# PIC32_WIZ810MJ.net
KiCad netlist of a schematic drawn in EAGLE
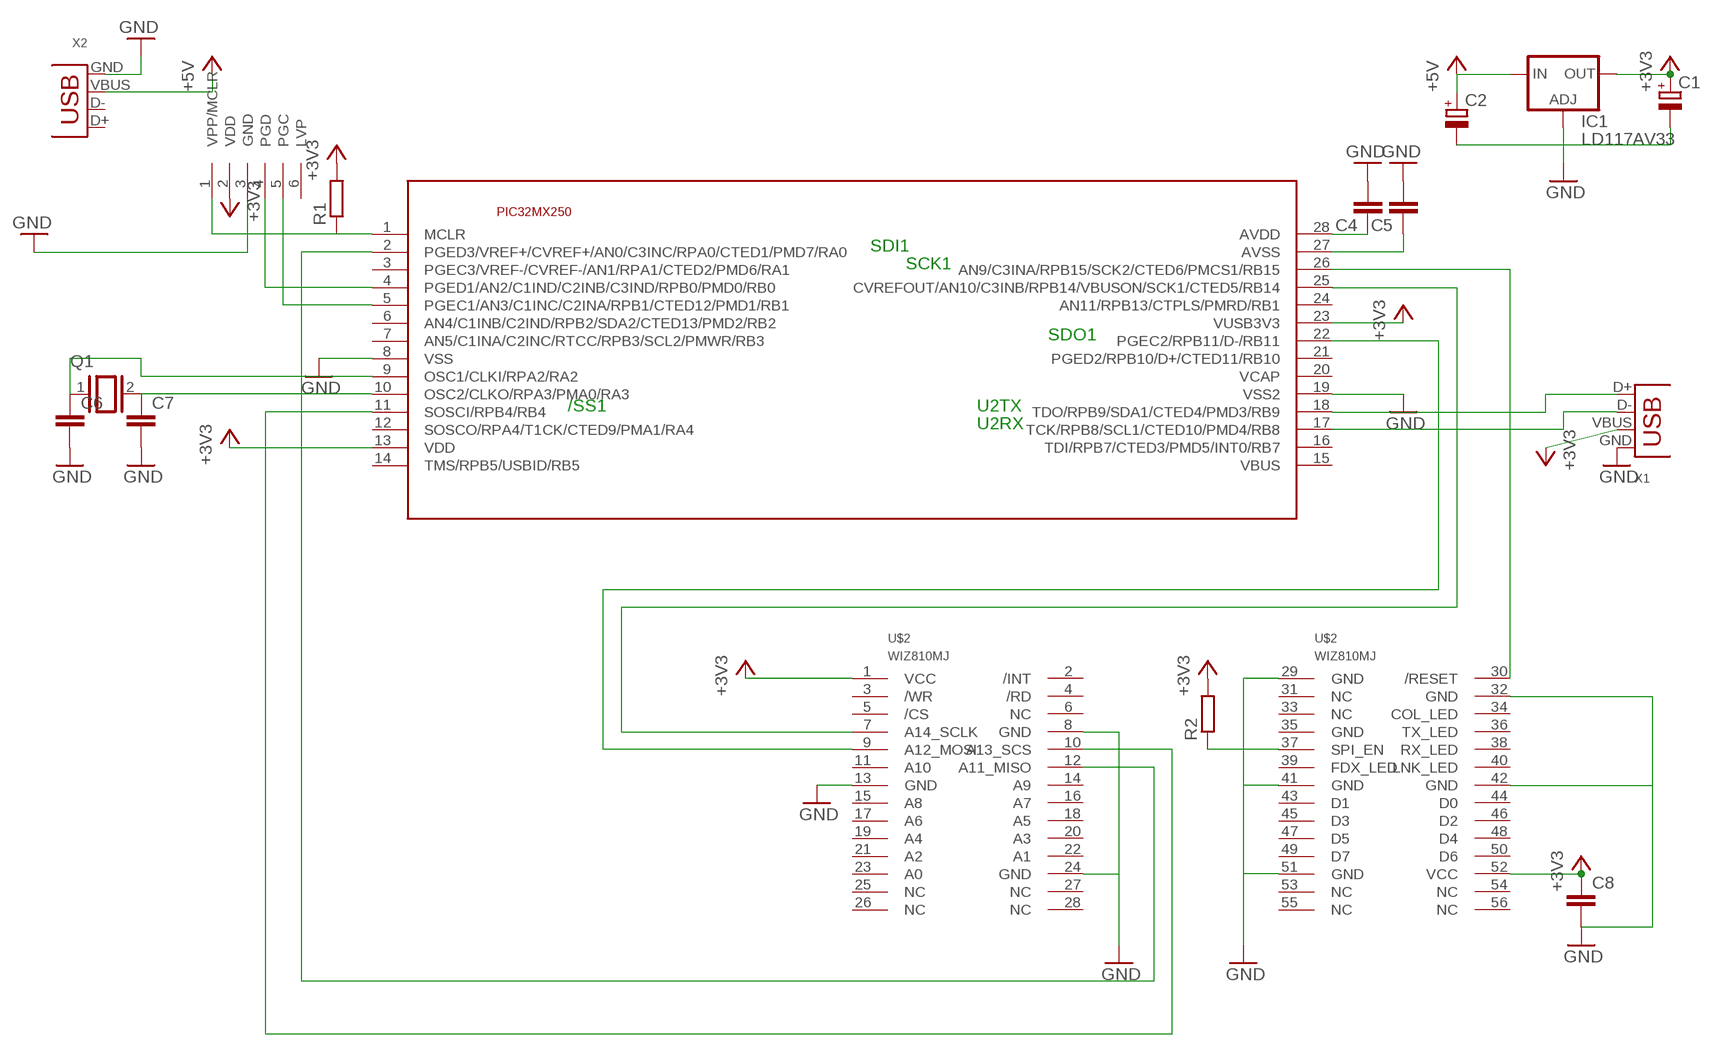
[diagram p0: schematic, sheet 1]

(export (version "E")
  (design (tool "Eeschema 10.0.6"))
  (components
    (comp (ref "C1")
      (value "CPOL-EUE3.5-10")
      (footprint "eagle-import:E3,5-10")
      (libsource (lib "eagle-import") (part "CPOL-EUE3.5-10"))
    )
    (comp (ref "C2")
      (value "CPOL-EUE3.5-10")
      (footprint "eagle-import:E3,5-10")
      (libsource (lib "eagle-import") (part "CPOL-EUE3.5-10"))
    )
    (comp (ref "C4")
      (value "C-EU050-055X075")
      (footprint "eagle-import:C050-055X075")
      (libsource (lib "eagle-import") (part "C-EU050-055X075"))
    )
    (comp (ref "C5")
      (value "C-EU050-055X075")
      (footprint "eagle-import:C050-055X075")
      (libsource (lib "eagle-import") (part "C-EU050-055X075"))
    )
    (comp (ref "C6")
      (value "C-EU025-025X050")
      (footprint "eagle-import:C025-025X050")
      (libsource (lib "eagle-import") (part "C-EU025-025X050"))
    )
    (comp (ref "C7")
      (value "C-EU025-025X050")
      (footprint "eagle-import:C025-025X050")
      (libsource (lib "eagle-import") (part "C-EU025-025X050"))
    )
    (comp (ref "C8")
      (value "C-EU050-055X075")
      (footprint "eagle-import:C050-055X075")
      (libsource (lib "eagle-import") (part "C-EU050-055X075"))
    )
    (comp (ref "IC1")
      (value "LD117AV33")
      (footprint "eagle-import:TO220L1")
      (libsource (lib "eagle-import") (part "LD117A?V33"))
    )
    (comp (ref "Q1")
      (value "XTAL/S")
      (footprint "eagle-import:QS")
      (libsource (lib "eagle-import") (part "XTAL/S"))
    )
    (comp (ref "R1")
      (value "R-EU_0204/5")
      (footprint "eagle-import:0204_5")
      (libsource (lib "eagle-import") (part "R-EU_0204/5"))
    )
    (comp (ref "R2")
      (value "R-EU_0204/5")
      (footprint "eagle-import:0204_5")
      (libsource (lib "eagle-import") (part "R-EU_0204/5"))
    )
    (comp (ref "U$1")
      (value "PIC32MX2XXDIP28_SLIM")
      (footprint "eagle-import:DIP254P762X508-28")
      (libsource (lib "eagle-import") (part "PIC32MX2XXDIP28_SLIM"))
    )
    (comp (ref "U$2")
      (value "WIZ810MJ")
      (footprint "eagle-import:WIZ810MJ")
      (libsource (lib "eagle-import") (part "WIZ810MJ"))
    )
    (comp (ref "U$3")
      (value "ICSP-6_6P")
      (footprint "eagle-import:1X06-CLEANBIG")
      (libsource (lib "eagle-import") (part "ICSP-6_6P"))
    )
    (comp (ref "X1")
      (value "USB-A-H")
      (footprint "eagle-import:USB-A-H")
      (libsource (lib "eagle-import") (part "USB-A-H"))
    )
    (comp (ref "X2")
      (value "USB-B-H")
      (footprint "eagle-import:USB-B-H")
      (libsource (lib "eagle-import") (part "USB-B-H"))
    )
  )
  (nets
    (net (code "1") (name "+3V3") (class "Default")
      (node (ref "C1") (pin "+") (pinfunction "+_+") (pintype "passive"))
      (node (ref "C8") (pin "1") (pinfunction "1_1") (pintype "passive"))
      (node (ref "IC1") (pin "2") (pinfunction "OUT_2") (pintype "passive"))
      (node (ref "R1") (pin "2") (pinfunction "2_2") (pintype "passive"))
      (node (ref "R2") (pin "2") (pinfunction "2_2") (pintype "passive"))
      (node (ref "U$1") (pin "13") (pinfunction "VDD_13") (pintype "power_in"))
      (node (ref "U$1") (pin "23") (pinfunction "VUSB3V3_23") (pintype "bidirectional"))
      (node (ref "U$2") (pin "1") (pinfunction "VCC_1") (pintype "bidirectional"))
      (node (ref "U$2") (pin "52") (pinfunction "VCC_52") (pintype "bidirectional"))
      (node (ref "U$3") (pin "2") (pinfunction "VDD_2") (pintype "bidirectional"))
      (node (ref "X1") (pin "VBUS") (pinfunction "VBUS_VBUS") (pintype "bidirectional"))
    )
    (net (code "2") (name "+5V") (class "Default")
      (node (ref "C2") (pin "+") (pinfunction "+_+") (pintype "passive"))
      (node (ref "IC1") (pin "3") (pinfunction "IN_3") (pintype "input"))
      (node (ref "X2") (pin "VBUS") (pinfunction "VBUS_VBUS") (pintype "bidirectional"))
    )
    (net (code "3") (name "GND") (class "Default")
      (node (ref "C1") (pin "-") (pinfunction "-_-") (pintype "passive"))
      (node (ref "C2") (pin "-") (pinfunction "-_-") (pintype "passive"))
      (node (ref "C4") (pin "2") (pinfunction "2_2") (pintype "passive"))
      (node (ref "C5") (pin "2") (pinfunction "2_2") (pintype "passive"))
      (node (ref "C6") (pin "2") (pinfunction "2_2") (pintype "passive"))
      (node (ref "C7") (pin "2") (pinfunction "2_2") (pintype "passive"))
      (node (ref "C8") (pin "2") (pinfunction "2_2") (pintype "passive"))
      (node (ref "IC1") (pin "1") (pinfunction "ADJ_1") (pintype "input"))
      (node (ref "U$1") (pin "19") (pinfunction "VSS2_19") (pintype "bidirectional"))
      (node (ref "U$1") (pin "8") (pinfunction "VSS_8") (pintype "power_in"))
      (node (ref "U$2") (pin "13") (pinfunction "GND_13") (pintype "bidirectional"))
      (node (ref "U$2") (pin "24") (pinfunction "GND_24") (pintype "bidirectional"))
      (node (ref "U$2") (pin "29") (pinfunction "GND_29") (pintype "bidirectional"))
      (node (ref "U$2") (pin "32") (pinfunction "GND_32") (pintype "bidirectional"))
      (node (ref "U$2") (pin "41") (pinfunction "GND_41") (pintype "bidirectional"))
      (node (ref "U$2") (pin "42") (pinfunction "GND_42") (pintype "bidirectional"))
      (node (ref "U$2") (pin "51") (pinfunction "GND_51") (pintype "bidirectional"))
      (node (ref "U$2") (pin "8") (pinfunction "GND_8") (pintype "bidirectional"))
      (node (ref "U$3") (pin "3") (pinfunction "GND_3") (pintype "bidirectional"))
      (node (ref "X1") (pin "GND") (pinfunction "GND_GND") (pintype "bidirectional"))
      (node (ref "X2") (pin "GND") (pinfunction "GND_GND") (pintype "bidirectional"))
    )
    (net (code "4") (name "Net-(U$1-AN9{slash}C3INA{slash}RPB15{slash}SCK2{slash}CTED6{slash}PMCS1{slash}RB15)") (class "Default")
      (node (ref "U$1") (pin "26") (pinfunction "AN9/C3INA/RPB15/SCK2/CTED6/PMCS1/RB15_26") (pintype "bidirectional"))
      (node (ref "U$2") (pin "30") (pinfunction "/RESET_30") (pintype "bidirectional"))
    )
    (net (code "5") (name "Net-(U$1-AVDD)") (class "Default")
      (node (ref "C4") (pin "1") (pinfunction "1_1") (pintype "passive"))
      (node (ref "U$1") (pin "28") (pinfunction "AVDD_28") (pintype "bidirectional"))
    )
    (net (code "6") (name "Net-(U$1-AVSS)") (class "Default")
      (node (ref "C5") (pin "1") (pinfunction "1_1") (pintype "passive"))
      (node (ref "U$1") (pin "27") (pinfunction "AVSS_27") (pintype "bidirectional"))
    )
    (net (code "7") (name "Net-(U$1-CVREFOUT{slash}AN10{slash}C3INB{slash}RPB14{slash}VBUSON{slash}SCK1{slash}CTED5{slash}RB14)") (class "Default")
      (node (ref "U$1") (pin "25") (pinfunction "CVREFOUT/AN10/C3INB/RPB14/VBUSON/SCK1/CTED5/RB14_25") (pintype "bidirectional"))
      (node (ref "U$2") (pin "7") (pinfunction "A14_SCLK_7") (pintype "bidirectional"))
    )
    (net (code "8") (name "Net-(U$1-MCLR)") (class "Default")
      (node (ref "R1") (pin "1") (pinfunction "1_1") (pintype "passive"))
      (node (ref "U$1") (pin "1") (pinfunction "MCLR_1") (pintype "bidirectional"))
      (node (ref "U$3") (pin "1") (pinfunction "VPP/MCLR_1") (pintype "bidirectional"))
    )
    (net (code "9") (name "Net-(U$1-OSC1{slash}CLKI{slash}RPA2{slash}RA2)") (class "Default")
      (node (ref "C6") (pin "1") (pinfunction "1_1") (pintype "passive"))
      (node (ref "Q1") (pin "1") (pinfunction "1_1") (pintype "passive"))
      (node (ref "U$1") (pin "9") (pinfunction "OSC1/CLKI/RPA2/RA2_9") (pintype "bidirectional"))
    )
    (net (code "10") (name "Net-(U$1-OSC2{slash}CLKO{slash}RPA3{slash}PMA0{slash}RA3)") (class "Default")
      (node (ref "C7") (pin "1") (pinfunction "1_1") (pintype "passive"))
      (node (ref "Q1") (pin "2") (pinfunction "2_2") (pintype "passive"))
      (node (ref "U$1") (pin "10") (pinfunction "OSC2/CLKO/RPA3/PMA0/RA3_10") (pintype "bidirectional"))
    )
    (net (code "11") (name "Net-(U$1-PGEC1{slash}AN3{slash}C1INC{slash}C2INA{slash}RPB1{slash}CTED12{slash}PMD1{slash}RB1)") (class "Default")
      (node (ref "U$1") (pin "5") (pinfunction "PGEC1/AN3/C1INC/C2INA/RPB1/CTED12/PMD1/RB1_5") (pintype "bidirectional"))
      (node (ref "U$3") (pin "5") (pinfunction "PGC_5") (pintype "bidirectional"))
    )
    (net (code "12") (name "Net-(U$1-PGEC2{slash}RPB11{slash}D-{slash}RB11)") (class "Default")
      (node (ref "U$1") (pin "22") (pinfunction "PGEC2/RPB11/D-/RB11_22") (pintype "bidirectional"))
      (node (ref "U$2") (pin "9") (pinfunction "A12_MOSI_9") (pintype "bidirectional"))
    )
    (net (code "13") (name "Net-(U$1-PGED1{slash}AN2{slash}C1IND{slash}C2INB{slash}C3IND{slash}RPB0{slash}PMD0{slash}RB0)") (class "Default")
      (node (ref "U$1") (pin "4") (pinfunction "PGED1/AN2/C1IND/C2INB/C3IND/RPB0/PMD0/RB0_4") (pintype "bidirectional"))
      (node (ref "U$3") (pin "4") (pinfunction "PGD_4") (pintype "bidirectional"))
    )
    (net (code "14") (name "Net-(U$1-PGED3{slash}VREF+{slash}CVREF+{slash}AN0{slash}C3INC{slash}RPA0{slash}CTED1{slash}PMD7{slash}RA0)") (class "Default")
      (node (ref "U$1") (pin "2") (pinfunction "PGED3/VREF+/CVREF+/AN0/C3INC/RPA0/CTED1/PMD7/RA0_2") (pintype "bidirectional"))
      (node (ref "U$2") (pin "12") (pinfunction "A11_MISO_12") (pintype "bidirectional"))
    )
    (net (code "15") (name "Net-(U$1-SOSCI{slash}RPB4{slash}RB4)") (class "Default")
      (node (ref "U$1") (pin "11") (pinfunction "SOSCI/RPB4/RB4_11") (pintype "bidirectional"))
      (node (ref "U$2") (pin "10") (pinfunction "A13_SCS_10") (pintype "bidirectional"))
    )
    (net (code "16") (name "Net-(U$1-TCK{slash}RPB8{slash}SCL1{slash}CTED10{slash}PMD4{slash}RB8)") (class "Default")
      (node (ref "U$1") (pin "17") (pinfunction "TCK/RPB8/SCL1/CTED10/PMD4/RB8_17") (pintype "bidirectional"))
      (node (ref "X1") (pin "D-") (pinfunction "D-_D-") (pintype "bidirectional"))
    )
    (net (code "17") (name "Net-(U$1-TDO{slash}RPB9{slash}SDA1{slash}CTED4{slash}PMD3{slash}RB9)") (class "Default")
      (node (ref "U$1") (pin "18") (pinfunction "TDO/RPB9/SDA1/CTED4/PMD3/RB9_18") (pintype "bidirectional"))
      (node (ref "X1") (pin "D+") (pinfunction "D+_D+") (pintype "bidirectional"))
    )
    (net (code "18") (name "Net-(U$2-SPI_EN)") (class "Default")
      (node (ref "R2") (pin "1") (pinfunction "1_1") (pintype "passive"))
      (node (ref "U$2") (pin "37") (pinfunction "SPI_EN_37") (pintype "bidirectional"))
    )
    (net (code "19") (name "unconnected-(U$1-AN4{slash}C1INB{slash}C2IND{slash}RPB2{slash}SDA2{slash}CTED13{slash}PMD2{slash}RB2-Pad6)") (class "Default")
      (node (ref "U$1") (pin "6") (pinfunction "AN4/C1INB/C2IND/RPB2/SDA2/CTED13/PMD2/RB2_6") (pintype "bidirectional"))
    )
    (net (code "20") (name "unconnected-(U$1-AN5{slash}C1INA{slash}C2INC{slash}RTCC{slash}RPB3{slash}SCL2{slash}PMWR{slash}RB3-Pad7)") (class "Default")
      (node (ref "U$1") (pin "7") (pinfunction "AN5/C1INA/C2INC/RTCC/RPB3/SCL2/PMWR/RB3_7") (pintype "bidirectional"))
    )
    (net (code "21") (name "unconnected-(U$1-AN11{slash}RPB13{slash}CTPLS{slash}PMRD{slash}RB1-Pad24)") (class "Default")
      (node (ref "U$1") (pin "24") (pinfunction "AN11/RPB13/CTPLS/PMRD/RB1_24") (pintype "bidirectional"))
    )
    (net (code "22") (name "unconnected-(U$1-PGEC3{slash}VREF-{slash}CVREF-{slash}AN1{slash}RPA1{slash}CTED2{slash}PMD6{slash}RA1-Pad3)") (class "Default")
      (node (ref "U$1") (pin "3") (pinfunction "PGEC3/VREF-/CVREF-/AN1/RPA1/CTED2/PMD6/RA1_3") (pintype "bidirectional"))
    )
    (net (code "23") (name "unconnected-(U$1-PGED2{slash}RPB10{slash}D+{slash}CTED11{slash}RB10-Pad21)") (class "Default")
      (node (ref "U$1") (pin "21") (pinfunction "PGED2/RPB10/D+/CTED11/RB10_21") (pintype "bidirectional"))
    )
    (net (code "24") (name "unconnected-(U$1-SOSCO{slash}RPA4{slash}T1CK{slash}CTED9{slash}PMA1{slash}RA4-Pad12)") (class "Default")
      (node (ref "U$1") (pin "12") (pinfunction "SOSCO/RPA4/T1CK/CTED9/PMA1/RA4_12") (pintype "bidirectional"))
    )
    (net (code "25") (name "unconnected-(U$1-TDI{slash}RPB7{slash}CTED3{slash}PMD5{slash}INT0{slash}RB7-Pad16)") (class "Default")
      (node (ref "U$1") (pin "16") (pinfunction "TDI/RPB7/CTED3/PMD5/INT0/RB7_16") (pintype "bidirectional"))
    )
    (net (code "26") (name "unconnected-(U$1-TMS{slash}RPB5{slash}USBID{slash}RB5-Pad14)") (class "Default")
      (node (ref "U$1") (pin "14") (pinfunction "TMS/RPB5/USBID/RB5_14") (pintype "bidirectional"))
    )
    (net (code "27") (name "unconnected-(U$1-VBUS-Pad15)") (class "Default")
      (node (ref "U$1") (pin "15") (pinfunction "VBUS_15") (pintype "bidirectional"))
    )
    (net (code "28") (name "unconnected-(U$1-VCAP-Pad20)") (class "Default")
      (node (ref "U$1") (pin "20") (pinfunction "VCAP_20") (pintype "bidirectional"))
    )
    (net (code "29") (name "unconnected-(U$2-A0-Pad23)") (class "Default")
      (node (ref "U$2") (pin "23") (pinfunction "A0_23") (pintype "bidirectional"))
    )
    (net (code "30") (name "unconnected-(U$2-A1-Pad22)") (class "Default")
      (node (ref "U$2") (pin "22") (pinfunction "A1_22") (pintype "bidirectional"))
    )
    (net (code "31") (name "unconnected-(U$2-A2-Pad21)") (class "Default")
      (node (ref "U$2") (pin "21") (pinfunction "A2_21") (pintype "bidirectional"))
    )
    (net (code "32") (name "unconnected-(U$2-A3-Pad20)") (class "Default")
      (node (ref "U$2") (pin "20") (pinfunction "A3_20") (pintype "bidirectional"))
    )
    (net (code "33") (name "unconnected-(U$2-A4-Pad19)") (class "Default")
      (node (ref "U$2") (pin "19") (pinfunction "A4_19") (pintype "bidirectional"))
    )
    (net (code "34") (name "unconnected-(U$2-A5-Pad18)") (class "Default")
      (node (ref "U$2") (pin "18") (pinfunction "A5_18") (pintype "bidirectional"))
    )
    (net (code "35") (name "unconnected-(U$2-A6-Pad17)") (class "Default")
      (node (ref "U$2") (pin "17") (pinfunction "A6_17") (pintype "bidirectional"))
    )
    (net (code "36") (name "unconnected-(U$2-A7-Pad16)") (class "Default")
      (node (ref "U$2") (pin "16") (pinfunction "A7_16") (pintype "bidirectional"))
    )
    (net (code "37") (name "unconnected-(U$2-A8-Pad15)") (class "Default")
      (node (ref "U$2") (pin "15") (pinfunction "A8_15") (pintype "bidirectional"))
    )
    (net (code "38") (name "unconnected-(U$2-A9-Pad14)") (class "Default")
      (node (ref "U$2") (pin "14") (pinfunction "A9_14") (pintype "bidirectional"))
    )
    (net (code "39") (name "unconnected-(U$2-A10-Pad11)") (class "Default")
      (node (ref "U$2") (pin "11") (pinfunction "A10_11") (pintype "bidirectional"))
    )
    (net (code "40") (name "unconnected-(U$2-COL_LED-Pad34)") (class "Default")
      (node (ref "U$2") (pin "34") (pinfunction "COL_LED_34") (pintype "bidirectional"))
    )
    (net (code "41") (name "unconnected-(U$2-D0-Pad44)") (class "Default")
      (node (ref "U$2") (pin "44") (pinfunction "D0_44") (pintype "bidirectional"))
    )
    (net (code "42") (name "unconnected-(U$2-D1-Pad43)") (class "Default")
      (node (ref "U$2") (pin "43") (pinfunction "D1_43") (pintype "bidirectional"))
    )
    (net (code "43") (name "unconnected-(U$2-D2-Pad46)") (class "Default")
      (node (ref "U$2") (pin "46") (pinfunction "D2_46") (pintype "bidirectional"))
    )
    (net (code "44") (name "unconnected-(U$2-D3-Pad45)") (class "Default")
      (node (ref "U$2") (pin "45") (pinfunction "D3_45") (pintype "bidirectional"))
    )
    (net (code "45") (name "unconnected-(U$2-D4-Pad48)") (class "Default")
      (node (ref "U$2") (pin "48") (pinfunction "D4_48") (pintype "bidirectional"))
    )
    (net (code "46") (name "unconnected-(U$2-D5-Pad47)") (class "Default")
      (node (ref "U$2") (pin "47") (pinfunction "D5_47") (pintype "bidirectional"))
    )
    (net (code "47") (name "unconnected-(U$2-D6-Pad50)") (class "Default")
      (node (ref "U$2") (pin "50") (pinfunction "D6_50") (pintype "bidirectional"))
    )
    (net (code "48") (name "unconnected-(U$2-D7-Pad49)") (class "Default")
      (node (ref "U$2") (pin "49") (pinfunction "D7_49") (pintype "bidirectional"))
    )
    (net (code "49") (name "unconnected-(U$2-FDX_LED-Pad39)") (class "Default")
      (node (ref "U$2") (pin "39") (pinfunction "FDX_LED_39") (pintype "bidirectional"))
    )
    (net (code "50") (name "unconnected-(U$2-GND-Pad35)") (class "Default")
      (node (ref "U$2") (pin "35") (pinfunction "GND_35") (pintype "bidirectional"))
    )
    (net (code "51") (name "unconnected-(U$2-LNK_LED-Pad40)") (class "Default")
      (node (ref "U$2") (pin "40") (pinfunction "LNK_LED_40") (pintype "bidirectional"))
    )
    (net (code "52") (name "unconnected-(U$2-NC-Pad6)") (class "Default")
      (node (ref "U$2") (pin "6") (pinfunction "NC_6") (pintype "bidirectional"))
    )
    (net (code "53") (name "unconnected-(U$2-NC-Pad25)") (class "Default")
      (node (ref "U$2") (pin "25") (pinfunction "NC_25") (pintype "bidirectional"))
    )
    (net (code "54") (name "unconnected-(U$2-NC-Pad26)") (class "Default")
      (node (ref "U$2") (pin "26") (pinfunction "NC_26") (pintype "bidirectional"))
    )
    (net (code "55") (name "unconnected-(U$2-NC-Pad27)") (class "Default")
      (node (ref "U$2") (pin "27") (pinfunction "NC_27") (pintype "bidirectional"))
    )
    (net (code "56") (name "unconnected-(U$2-NC-Pad28)") (class "Default")
      (node (ref "U$2") (pin "28") (pinfunction "NC_28") (pintype "bidirectional"))
    )
    (net (code "57") (name "unconnected-(U$2-NC-Pad31)") (class "Default")
      (node (ref "U$2") (pin "31") (pinfunction "NC_31") (pintype "bidirectional"))
    )
    (net (code "58") (name "unconnected-(U$2-NC-Pad33)") (class "Default")
      (node (ref "U$2") (pin "33") (pinfunction "NC_33") (pintype "bidirectional"))
    )
    (net (code "59") (name "unconnected-(U$2-NC-Pad53)") (class "Default")
      (node (ref "U$2") (pin "53") (pinfunction "NC_53") (pintype "bidirectional"))
    )
    (net (code "60") (name "unconnected-(U$2-NC-Pad54)") (class "Default")
      (node (ref "U$2") (pin "54") (pinfunction "NC_54") (pintype "bidirectional"))
    )
    (net (code "61") (name "unconnected-(U$2-NC-Pad55)") (class "Default")
      (node (ref "U$2") (pin "55") (pinfunction "NC_55") (pintype "bidirectional"))
    )
    (net (code "62") (name "unconnected-(U$2-NC-Pad56)") (class "Default")
      (node (ref "U$2") (pin "56") (pinfunction "NC_56") (pintype "bidirectional"))
    )
    (net (code "63") (name "unconnected-(U$2-RX_LED-Pad38)") (class "Default")
      (node (ref "U$2") (pin "38") (pinfunction "RX_LED_38") (pintype "bidirectional"))
    )
    (net (code "64") (name "unconnected-(U$2-TX_LED-Pad36)") (class "Default")
      (node (ref "U$2") (pin "36") (pinfunction "TX_LED_36") (pintype "bidirectional"))
    )
    (net (code "65") (name "unconnected-(U$2-{slash}CS-Pad5)") (class "Default")
      (node (ref "U$2") (pin "5") (pinfunction "/CS_5") (pintype "bidirectional"))
    )
    (net (code "66") (name "unconnected-(U$2-{slash}INT-Pad2)") (class "Default")
      (node (ref "U$2") (pin "2") (pinfunction "/INT_2") (pintype "bidirectional"))
    )
    (net (code "67") (name "unconnected-(U$2-{slash}RD-Pad4)") (class "Default")
      (node (ref "U$2") (pin "4") (pinfunction "/RD_4") (pintype "bidirectional"))
    )
    (net (code "68") (name "unconnected-(U$2-{slash}WR-Pad3)") (class "Default")
      (node (ref "U$2") (pin "3") (pinfunction "/WR_3") (pintype "bidirectional"))
    )
    (net (code "69") (name "unconnected-(U$3-LVP-Pad6)") (class "Default")
      (node (ref "U$3") (pin "6") (pinfunction "LVP_6") (pintype "bidirectional"))
    )
    (net (code "70") (name "unconnected-(X2-PadD+)") (class "Default")
      (node (ref "X2") (pin "D+") (pinfunction "D+_D+") (pintype "bidirectional"))
    )
    (net (code "71") (name "unconnected-(X2-PadD-)") (class "Default")
      (node (ref "X2") (pin "D-") (pinfunction "D-_D-") (pintype "bidirectional"))
    )
  )
)
